# mySensorsRS485GW_front.net
KiCad netlist of a schematic drawn in EAGLE
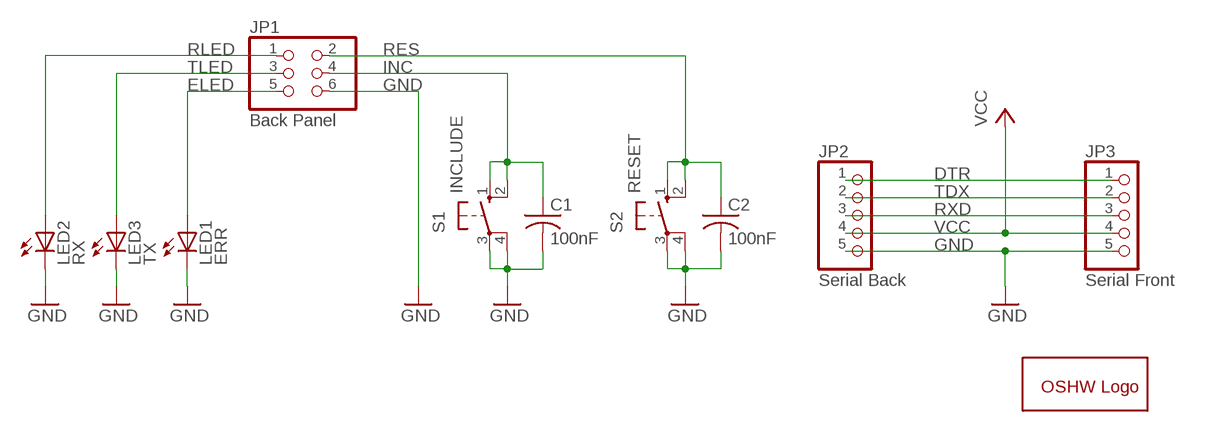
[diagram p0: schematic, sheet 1]

(export (version "E")
  (design (tool "Eeschema 10.0.6"))
  (components
    (comp (ref "C1")
      (value "100nF")
      (footprint "eagle-import:C025-025X050")
      (libsource (lib "eagle-import") (part "C-US025-025X050"))
    )
    (comp (ref "C2")
      (value "100nF")
      (footprint "eagle-import:C025-025X050")
      (libsource (lib "eagle-import") (part "C-US025-025X050"))
    )
    (comp (ref "GOLD_ORB_SM1")
      (value "OSHWLOGOLOGO5MM")
      (footprint "eagle-import:OSHW_5MM")
      (libsource (lib "eagle-import") (part "OSHWLOGOLOGO5MM"))
    )
    (comp (ref "JP1")
      (value "Back Panel")
      (footprint "eagle-import:2X03")
      (libsource (lib "eagle-import") (part "PINHD-2X3"))
    )
    (comp (ref "JP2")
      (value "Serial Back")
      (footprint "eagle-import:1X05")
      (libsource (lib "eagle-import") (part "PINHD-1X5"))
    )
    (comp (ref "JP3")
      (value "Serial Front")
      (footprint "eagle-import:1X05")
      (libsource (lib "eagle-import") (part "PINHD-1X5"))
    )
    (comp (ref "LED1")
      (value "ERR")
      (footprint "eagle-import:LED3MM")
      (libsource (lib "eagle-import") (part "LED3MM"))
    )
    (comp (ref "LED2")
      (value "RX")
      (footprint "eagle-import:LED3MM")
      (libsource (lib "eagle-import") (part "LED3MM"))
    )
    (comp (ref "LED3")
      (value "TX")
      (footprint "eagle-import:LED3MM")
      (libsource (lib "eagle-import") (part "LED3MM"))
    )
    (comp (ref "S1")
      (value "INCLUDE")
      (footprint "eagle-import:B3F-10XX")
      (fields (field (name "MPN") "B3F-1000"))
      (libsource (lib "eagle-import") (part "10-XX"))
    )
    (comp (ref "S2")
      (value "RESET")
      (footprint "eagle-import:B3F-10XX")
      (fields (field (name "MPN") "B3F-1000"))
      (libsource (lib "eagle-import") (part "10-XX"))
    )
  )
  (nets
    (net (code "1") (name "/DTR") (class "Default")
      (node (ref "JP2") (pin "1") (pinfunction "1_1") (pintype "passive"))
      (node (ref "JP3") (pin "1") (pinfunction "1_1") (pintype "passive"))
    )
    (net (code "2") (name "/ELED") (class "Default")
      (node (ref "JP1") (pin "5") (pinfunction "5_5") (pintype "passive"))
      (node (ref "LED1") (pin "A") (pinfunction "A_A") (pintype "passive"))
    )
    (net (code "3") (name "/INC") (class "Default")
      (node (ref "C1") (pin "1") (pinfunction "1_1") (pintype "passive"))
      (node (ref "JP1") (pin "4") (pinfunction "4_4") (pintype "passive"))
      (node (ref "S1") (pin "1") (pinfunction "S_1") (pintype "passive"))
      (node (ref "S1") (pin "2") (pinfunction "S1_2") (pintype "passive"))
    )
    (net (code "4") (name "/RES") (class "Default")
      (node (ref "C2") (pin "1") (pinfunction "1_1") (pintype "passive"))
      (node (ref "JP1") (pin "2") (pinfunction "2_2") (pintype "passive"))
      (node (ref "S2") (pin "1") (pinfunction "S_1") (pintype "passive"))
      (node (ref "S2") (pin "2") (pinfunction "S1_2") (pintype "passive"))
    )
    (net (code "5") (name "/RLED") (class "Default")
      (node (ref "JP1") (pin "1") (pinfunction "1_1") (pintype "passive"))
      (node (ref "LED2") (pin "A") (pinfunction "A_A") (pintype "passive"))
    )
    (net (code "6") (name "/RXD") (class "Default")
      (node (ref "JP2") (pin "3") (pinfunction "3_3") (pintype "passive"))
      (node (ref "JP3") (pin "3") (pinfunction "3_3") (pintype "passive"))
    )
    (net (code "7") (name "/TDX") (class "Default")
      (node (ref "JP2") (pin "2") (pinfunction "2_2") (pintype "passive"))
      (node (ref "JP3") (pin "2") (pinfunction "2_2") (pintype "passive"))
    )
    (net (code "8") (name "/TLED") (class "Default")
      (node (ref "JP1") (pin "3") (pinfunction "3_3") (pintype "passive"))
      (node (ref "LED3") (pin "A") (pinfunction "A_A") (pintype "passive"))
    )
    (net (code "9") (name "GND") (class "Default")
      (node (ref "C1") (pin "2") (pinfunction "2_2") (pintype "passive"))
      (node (ref "C2") (pin "2") (pinfunction "2_2") (pintype "passive"))
      (node (ref "JP1") (pin "6") (pinfunction "6_6") (pintype "passive"))
      (node (ref "JP2") (pin "5") (pinfunction "5_5") (pintype "passive"))
      (node (ref "JP3") (pin "5") (pinfunction "5_5") (pintype "passive"))
      (node (ref "LED1") (pin "K") (pinfunction "C_K") (pintype "passive"))
      (node (ref "LED2") (pin "K") (pinfunction "C_K") (pintype "passive"))
      (node (ref "LED3") (pin "K") (pinfunction "C_K") (pintype "passive"))
      (node (ref "S1") (pin "3") (pinfunction "P_3") (pintype "passive"))
      (node (ref "S1") (pin "4") (pinfunction "P1_4") (pintype "passive"))
      (node (ref "S2") (pin "3") (pinfunction "P_3") (pintype "passive"))
      (node (ref "S2") (pin "4") (pinfunction "P1_4") (pintype "passive"))
    )
    (net (code "10") (name "VCC") (class "Default")
      (node (ref "JP2") (pin "4") (pinfunction "4_4") (pintype "passive"))
      (node (ref "JP3") (pin "4") (pinfunction "4_4") (pintype "passive"))
    )
  )
)
